# source_eagle.net
KiCad netlist of a schematic drawn in EAGLE
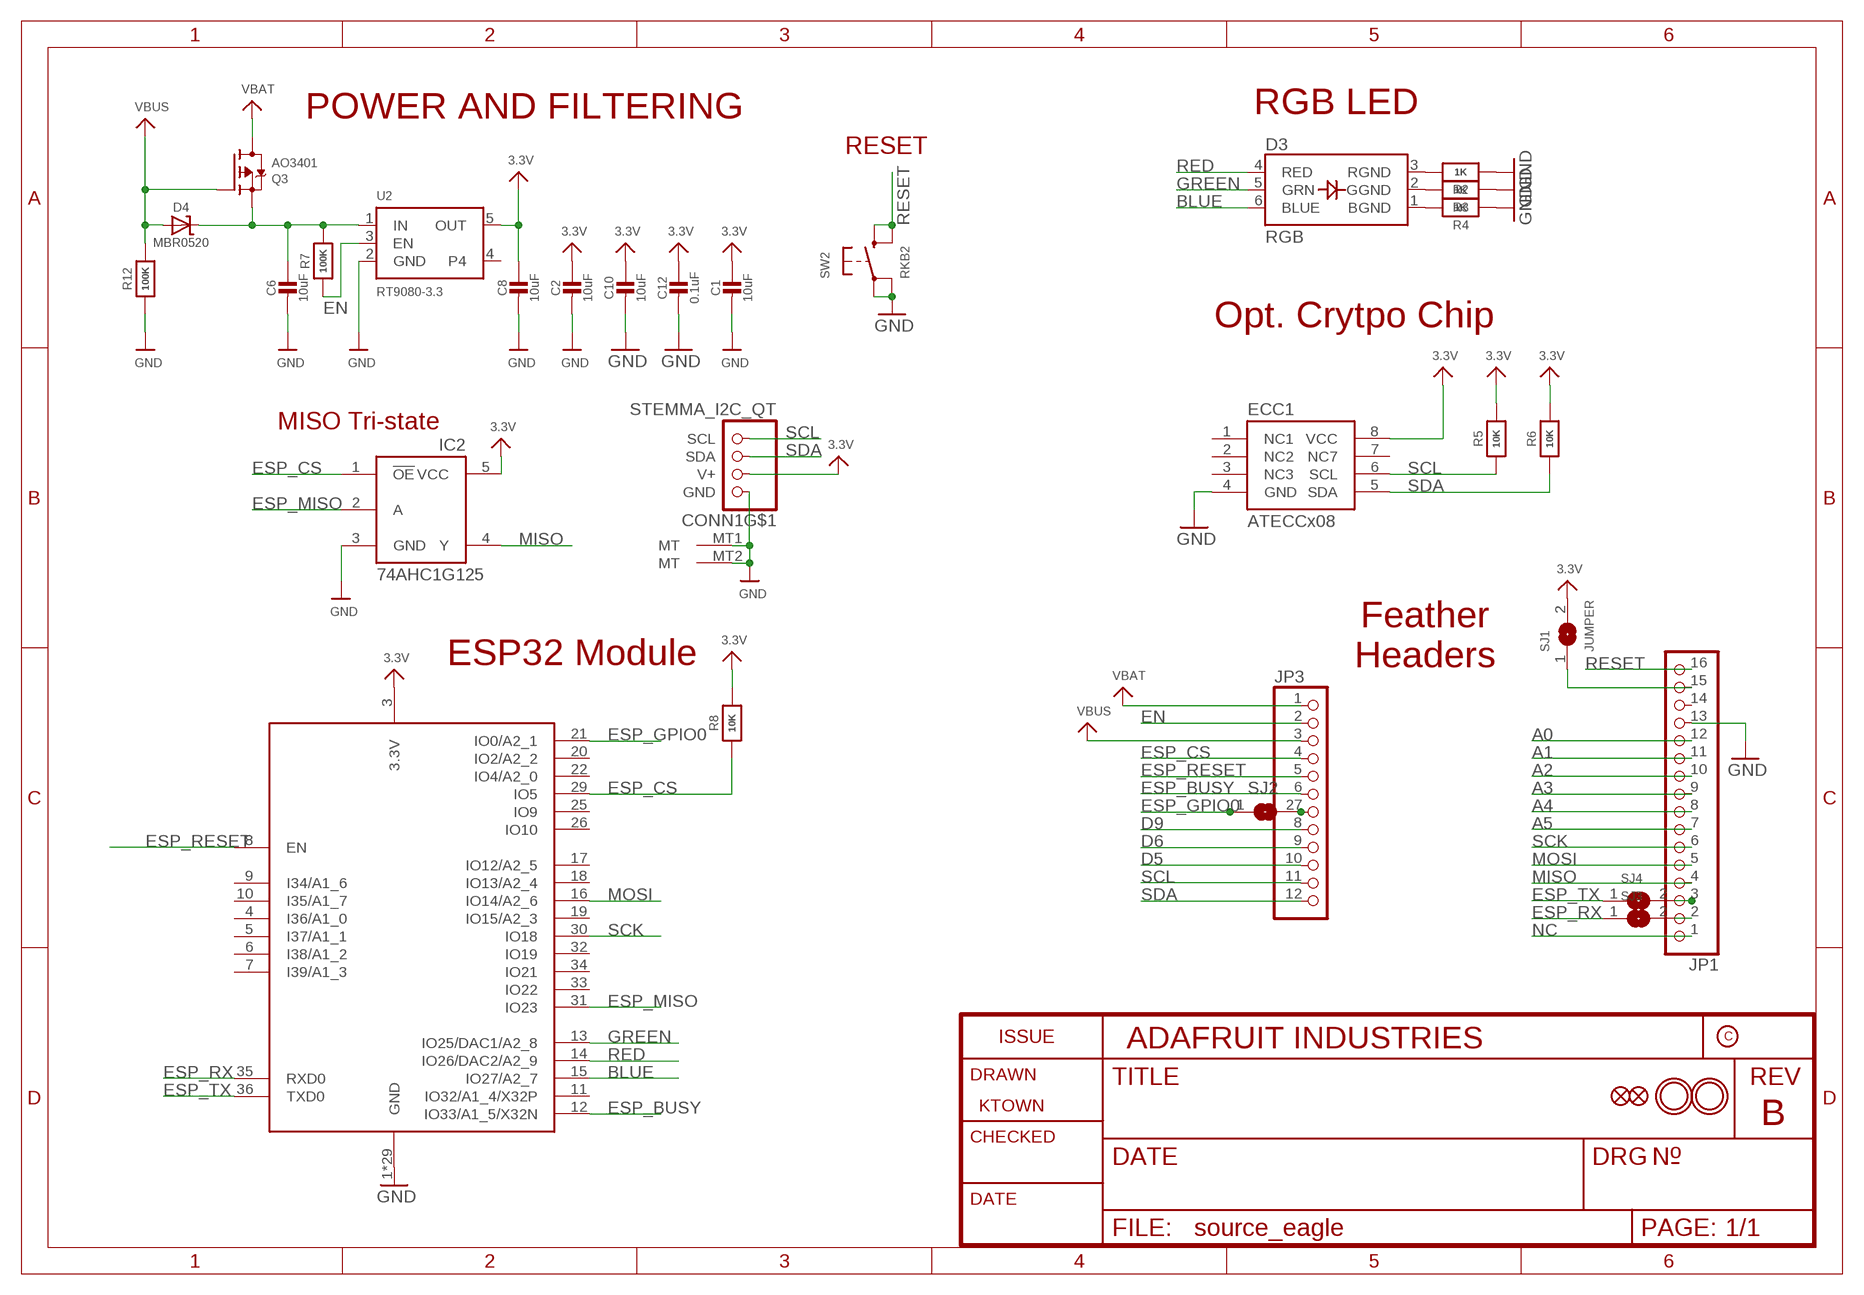
[diagram p0: schematic, sheet 1]

(export (version "E")
  (design (tool "Eeschema 10.0.6"))
  (components
    (comp (ref "C1")
      (value "10uF")
      (footprint "eagle-import:0805-NO")
      (libsource (lib "eagle-import") (part "CAP_CERAMIC0805-NOOUTLINE"))
    )
    (comp (ref "C2")
      (value "10uF")
      (footprint "eagle-import:0805-NO")
      (libsource (lib "eagle-import") (part "CAP_CERAMIC0805-NOOUTLINE"))
    )
    (comp (ref "C6")
      (value "10uF")
      (footprint "eagle-import:0805-NO")
      (libsource (lib "eagle-import") (part "CAP_CERAMIC0805-NOOUTLINE"))
    )
    (comp (ref "C8")
      (value "10uF")
      (footprint "eagle-import:0805-NO")
      (fields (field (name "REV") "C"))
      (libsource (lib "eagle-import") (part "CAP_CERAMIC0805-NOOUTLINE"))
    )
    (comp (ref "C10")
      (value "10uF")
      (footprint "eagle-import:0805-NO")
      (libsource (lib "eagle-import") (part "CAP_CERAMIC0805-NOOUTLINE"))
    )
    (comp (ref "C12")
      (value "0.1uF")
      (footprint "eagle-import:0603-NO")
      (libsource (lib "eagle-import") (part "CAP_CERAMIC0603_NO"))
    )
    (comp (ref "CONN1")
      (value "STEMMA_I2C_QT")
      (footprint "eagle-import:JST_SH4")
      (libsource (lib "eagle-import") (part "STEMMA_I2C_QT"))
    )
    (comp (ref "D3")
      (value "RGB")
      (footprint "eagle-import:RGBLED_3535_PLCC6")
      (libsource (lib "eagle-import") (part "LED_RGB_PLCC63535"))
    )
    (comp (ref "D4")
      (value "MBR0520")
      (footprint "eagle-import:SOD-123")
      (libsource (lib "eagle-import") (part "DIODE-SCHOTTKYSOD-123"))
    )
    (comp (ref "ECC1")
      (value "ATECCx08")
      (footprint "eagle-import:SOIC8")
      (libsource (lib "eagle-import") (part "ATECC108"))
    )
    (comp (ref "IC2")
      (value "74AHC1G125")
      (footprint "eagle-import:SOT23-5L")
      (libsource (lib "eagle-import") (part "74AHC1G125"))
    )
    (comp (ref "JP1")
      (value "HEADER-1X16_MIN")
      (footprint "eagle-import:1X16_ROUND_MIN")
      (libsource (lib "eagle-import") (part "HEADER-1X16_MIN"))
    )
    (comp (ref "JP3")
      (value "HEADER-1X12_MIN")
      (footprint "eagle-import:1X12_ROUND_MIN")
      (libsource (lib "eagle-import") (part "HEADER-1X12_MIN"))
    )
    (comp (ref "Q3")
      (value "AO3401")
      (footprint "eagle-import:SOT23-R")
      (libsource (lib "eagle-import") (part "MOSFET-P"))
    )
    (comp (ref "R2")
      (value "1K")
      (footprint "eagle-import:0603-NO")
      (libsource (lib "eagle-import") (part "RESISTOR_0603_NOOUT"))
    )
    (comp (ref "R3")
      (value "1K")
      (footprint "eagle-import:0603-NO")
      (libsource (lib "eagle-import") (part "RESISTOR_0603_NOOUT"))
    )
    (comp (ref "R4")
      (value "1K")
      (footprint "eagle-import:0603-NO")
      (libsource (lib "eagle-import") (part "RESISTOR_0603_NOOUT"))
    )
    (comp (ref "R5")
      (value "10K")
      (footprint "eagle-import:0603-NO")
      (libsource (lib "eagle-import") (part "RESISTOR_0603_NOOUT"))
    )
    (comp (ref "R6")
      (value "10K")
      (footprint "eagle-import:0603-NO")
      (libsource (lib "eagle-import") (part "RESISTOR_0603_NOOUT"))
    )
    (comp (ref "R7")
      (value "100K")
      (footprint "eagle-import:0603-NO")
      (libsource (lib "eagle-import") (part "RESISTOR_0603_NOOUT"))
    )
    (comp (ref "R8")
      (value "10K")
      (footprint "eagle-import:0603-NO")
      (libsource (lib "eagle-import") (part "RESISTOR_0603_NOOUT"))
    )
    (comp (ref "R12")
      (value "100K")
      (footprint "eagle-import:0603-NO")
      (libsource (lib "eagle-import") (part "RESISTOR_0603_NOOUT"))
    )
    (comp (ref "SJ1")
      (value "JUMPER")
      (footprint "eagle-import:SOLDERJUMPER_ARROW_NOPASTE")
      (libsource (lib "eagle-import") (part "SOLDERJUMPER"))
    )
    (comp (ref "SJ2")
      (value "SOLDERJUMPER")
      (footprint "eagle-import:SOLDERJUMPER_ARROW_NOPASTE")
      (libsource (lib "eagle-import") (part "SOLDERJUMPER"))
    )
    (comp (ref "SJ3")
      (value "SOLDERJUMPER")
      (footprint "eagle-import:SOLDERJUMPER_ARROW_NOPASTE")
      (libsource (lib "eagle-import") (part "SOLDERJUMPER"))
    )
    (comp (ref "SJ4")
      (value "SOLDERJUMPER")
      (footprint "eagle-import:SOLDERJUMPER_ARROW_NOPASTE")
      (libsource (lib "eagle-import") (part "SOLDERJUMPER"))
    )
    (comp (ref "SW2")
      (value "RKB2")
      (footprint "eagle-import:BTN_RKB2_4.6X2.8")
      (libsource (lib "eagle-import") (part "SWITCH_TACT_SMT_RKB2"))
    )
    (comp (ref "U$31")
      (value "MOUNTINGHOLE2.5")
      (footprint "eagle-import:MOUNTINGHOLE_2.5_PLATED")
      (libsource (lib "eagle-import") (part "MOUNTINGHOLE2.5"))
    )
    (comp (ref "U$32")
      (value "MOUNTINGHOLE2.5")
      (footprint "eagle-import:MOUNTINGHOLE_2.5_PLATED")
      (libsource (lib "eagle-import") (part "MOUNTINGHOLE2.5"))
    )
    (comp (ref "U$34")
      (value "FIDUCIAL_1MM")
      (footprint "eagle-import:FIDUCIAL_1MM")
      (libsource (lib "eagle-import") (part "FIDUCIAL_1MM"))
    )
    (comp (ref "U$35")
      (value "FIDUCIAL_1MM")
      (footprint "eagle-import:FIDUCIAL_1MM")
      (libsource (lib "eagle-import") (part "FIDUCIAL_1MM"))
    )
    (comp (ref "U2")
      (value "RT9080-3.3")
      (footprint "eagle-import:SOT23-5")
      (fields (field (name "JLC_ROTATION") "0"))
      (libsource (lib "eagle-import") (part "VREG_SOT23-5"))
    )
    (comp (ref "X1")
      (value "ESP32-MINI-1")
      (footprint "eagle-import:ESP32-MINI-1")
      (libsource (lib "eagle-import") (part "ESP32-MINI-1"))
    )
  )
  (nets
    (net (code "1") (name "/A0") (class "Default")
      (node (ref "JP1") (pin "12") (pinfunction "12_12") (pintype "passive"))
    )
    (net (code "2") (name "/A1") (class "Default")
      (node (ref "JP1") (pin "11") (pinfunction "11_11") (pintype "passive"))
    )
    (net (code "3") (name "/A2") (class "Default")
      (node (ref "JP1") (pin "10") (pinfunction "10_10") (pintype "passive"))
    )
    (net (code "4") (name "/A3") (class "Default")
      (node (ref "JP1") (pin "9") (pinfunction "9_9") (pintype "passive"))
    )
    (net (code "5") (name "/A4") (class "Default")
      (node (ref "JP1") (pin "8") (pinfunction "8_8") (pintype "passive"))
    )
    (net (code "6") (name "/A5") (class "Default")
      (node (ref "JP1") (pin "7") (pinfunction "7_7") (pintype "passive"))
    )
    (net (code "7") (name "/BLUE") (class "Default")
      (node (ref "D3") (pin "6") (pinfunction "BLUE_6") (pintype "bidirectional"))
      (node (ref "X1") (pin "15") (pinfunction "IO27/A2_7_15") (pintype "bidirectional"))
    )
    (net (code "8") (name "/D5") (class "Default")
      (node (ref "JP3") (pin "10") (pinfunction "10_10") (pintype "passive"))
    )
    (net (code "9") (name "/D6") (class "Default")
      (node (ref "JP3") (pin "9") (pinfunction "9_9") (pintype "passive"))
    )
    (net (code "10") (name "/D9") (class "Default")
      (node (ref "JP3") (pin "8") (pinfunction "8_8") (pintype "passive"))
    )
    (net (code "11") (name "/EN") (class "Default")
      (node (ref "JP3") (pin "2") (pinfunction "2_2") (pintype "passive"))
      (node (ref "R7") (pin "1") (pinfunction "1_1") (pintype "passive"))
      (node (ref "U2") (pin "3") (pinfunction "EN_3") (pintype "input"))
    )
    (net (code "12") (name "/ESP_BUSY") (class "Default")
      (node (ref "JP3") (pin "6") (pinfunction "6_6") (pintype "passive"))
      (node (ref "X1") (pin "12") (pinfunction "IO33/A1_5/X32N_12") (pintype "bidirectional"))
    )
    (net (code "13") (name "/ESP_CS") (class "Default")
      (node (ref "IC2") (pin "1") (pinfunction "~{OE}_1") (pintype "input"))
      (node (ref "JP3") (pin "4") (pinfunction "4_4") (pintype "passive"))
      (node (ref "R8") (pin "1") (pinfunction "1_1") (pintype "passive"))
      (node (ref "X1") (pin "29") (pinfunction "IO5_29") (pintype "bidirectional"))
    )
    (net (code "14") (name "/ESP_GPIO0") (class "Default")
      (node (ref "SJ2") (pin "1") (pinfunction "1_1") (pintype "passive"))
      (node (ref "X1") (pin "21") (pinfunction "IO0/A2_1_21") (pintype "bidirectional"))
    )
    (net (code "15") (name "/ESP_MISO") (class "Default")
      (node (ref "IC2") (pin "2") (pinfunction "A_2") (pintype "input"))
      (node (ref "X1") (pin "31") (pinfunction "IO23_31") (pintype "bidirectional"))
    )
    (net (code "16") (name "/ESP_RESET") (class "Default")
      (node (ref "JP3") (pin "5") (pinfunction "5_5") (pintype "passive"))
      (node (ref "X1") (pin "8") (pinfunction "EN_8") (pintype "input"))
    )
    (net (code "17") (name "/ESP_RX") (class "Default")
      (node (ref "SJ3") (pin "1") (pinfunction "1_1") (pintype "passive"))
      (node (ref "X1") (pin "35") (pinfunction "RXD0_35") (pintype "input"))
    )
    (net (code "18") (name "/ESP_TX") (class "Default")
      (node (ref "SJ4") (pin "1") (pinfunction "1_1") (pintype "passive"))
      (node (ref "X1") (pin "36") (pinfunction "TXD0_36") (pintype "output"))
    )
    (net (code "19") (name "/GREEN") (class "Default")
      (node (ref "D3") (pin "5") (pinfunction "GRN_5") (pintype "bidirectional"))
      (node (ref "X1") (pin "13") (pinfunction "IO25/DAC1/A2_8_13") (pintype "bidirectional"))
    )
    (net (code "20") (name "/MISO") (class "Default")
      (node (ref "IC2") (pin "4") (pinfunction "Y_4") (pintype "output"))
      (node (ref "JP1") (pin "4") (pinfunction "4_4") (pintype "passive"))
    )
    (net (code "21") (name "/MOSI") (class "Default")
      (node (ref "JP1") (pin "5") (pinfunction "5_5") (pintype "passive"))
      (node (ref "X1") (pin "16") (pinfunction "IO14/A2_6_16") (pintype "bidirectional"))
    )
    (net (code "22") (name "/NC") (class "Default")
      (node (ref "JP1") (pin "1") (pinfunction "1_1") (pintype "passive"))
    )
    (net (code "23") (name "/RED") (class "Default")
      (node (ref "D3") (pin "4") (pinfunction "RED_4") (pintype "bidirectional"))
      (node (ref "X1") (pin "14") (pinfunction "IO26/DAC2/A2_9_14") (pintype "bidirectional"))
    )
    (net (code "24") (name "/RESET") (class "Default")
      (node (ref "JP1") (pin "16") (pinfunction "16_16") (pintype "passive"))
      (node (ref "SW2") (pin "B") (pinfunction "S_B") (pintype "passive"))
      (node (ref "SW2") (pin "B'") (pinfunction "S1_B'") (pintype "passive"))
    )
    (net (code "25") (name "/SCK") (class "Default")
      (node (ref "JP1") (pin "6") (pinfunction "6_6") (pintype "passive"))
      (node (ref "X1") (pin "30") (pinfunction "IO18_30") (pintype "bidirectional"))
    )
    (net (code "26") (name "/SCL") (class "Default")
      (node (ref "CONN1") (pin "4") (pinfunction "SCL_4") (pintype "passive"))
      (node (ref "ECC1") (pin "6") (pinfunction "SCL_6") (pintype "bidirectional"))
      (node (ref "JP3") (pin "11") (pinfunction "11_11") (pintype "passive"))
      (node (ref "R5") (pin "1") (pinfunction "1_1") (pintype "passive"))
    )
    (net (code "27") (name "/SDA") (class "Default")
      (node (ref "CONN1") (pin "3") (pinfunction "SDA_3") (pintype "passive"))
      (node (ref "ECC1") (pin "5") (pinfunction "SDA_5") (pintype "bidirectional"))
      (node (ref "JP3") (pin "12") (pinfunction "12_12") (pintype "passive"))
      (node (ref "R6") (pin "1") (pinfunction "1_1") (pintype "passive"))
    )
    (net (code "28") (name "3.3V") (class "Default")
      (node (ref "C1") (pin "1") (pinfunction "1_1") (pintype "passive"))
      (node (ref "C10") (pin "1") (pinfunction "1_1") (pintype "passive"))
      (node (ref "C12") (pin "1") (pinfunction "1_1") (pintype "passive"))
      (node (ref "C2") (pin "1") (pinfunction "1_1") (pintype "passive"))
      (node (ref "C8") (pin "1") (pinfunction "1_1") (pintype "passive"))
      (node (ref "CONN1") (pin "2") (pinfunction "V+_2") (pintype "passive"))
      (node (ref "ECC1") (pin "8") (pinfunction "VCC_8") (pintype "power_in"))
      (node (ref "IC2") (pin "5") (pinfunction "VCC_5") (pintype "power_in"))
      (node (ref "R5") (pin "2") (pinfunction "2_2") (pintype "passive"))
      (node (ref "R6") (pin "2") (pinfunction "2_2") (pintype "passive"))
      (node (ref "R8") (pin "2") (pinfunction "2_2") (pintype "passive"))
      (node (ref "SJ1") (pin "2") (pinfunction "2_2") (pintype "passive"))
      (node (ref "U2") (pin "5") (pinfunction "OUT_5") (pintype "power_in"))
      (node (ref "X1") (pin "3") (pinfunction "3.3V_3") (pintype "passive"))
    )
    (net (code "29") (name "GND") (class "Default")
      (node (ref "C1") (pin "2") (pinfunction "2_2") (pintype "passive"))
      (node (ref "C10") (pin "2") (pinfunction "2_2") (pintype "passive"))
      (node (ref "C12") (pin "2") (pinfunction "2_2") (pintype "passive"))
      (node (ref "C2") (pin "2") (pinfunction "2_2") (pintype "passive"))
      (node (ref "C6") (pin "2") (pinfunction "2_2") (pintype "passive"))
      (node (ref "C8") (pin "2") (pinfunction "2_2") (pintype "passive"))
      (node (ref "CONN1") (pin "1") (pinfunction "GND_1") (pintype "passive"))
      (node (ref "CONN1") (pin "MT1") (pinfunction "MT_MT1") (pintype "bidirectional"))
      (node (ref "CONN1") (pin "MT2") (pinfunction "MT_MT2") (pintype "bidirectional"))
      (node (ref "ECC1") (pin "4") (pinfunction "GND_4") (pintype "power_in"))
      (node (ref "IC2") (pin "3") (pinfunction "GND_3") (pintype "power_in"))
      (node (ref "JP1") (pin "13") (pinfunction "13_13") (pintype "passive"))
      (node (ref "R12") (pin "1") (pinfunction "1_1") (pintype "passive"))
      (node (ref "R2") (pin "1") (pinfunction "1_1") (pintype "passive"))
      (node (ref "R3") (pin "1") (pinfunction "1_1") (pintype "passive"))
      (node (ref "R4") (pin "1") (pinfunction "1_1") (pintype "passive"))
      (node (ref "SW2") (pin "A") (pinfunction "P_A") (pintype "passive"))
      (node (ref "SW2") (pin "A'") (pinfunction "P1_A'") (pintype "passive"))
      (node (ref "U2") (pin "2") (pinfunction "GND_2") (pintype "power_in"))
      (node (ref "X1") (pin "1") (pinfunction "GND_1") (pintype "passive"))
      (node (ref "X1") (pin "2") (pinfunction "GND_2") (pintype "passive"))
      (node (ref "X1") (pin "27") (pinfunction "GND_27") (pintype "passive"))
      (node (ref "X1") (pin "38") (pinfunction "GND_38") (pintype "passive"))
      (node (ref "X1") (pin "39") (pinfunction "GND_39") (pintype "passive"))
      (node (ref "X1") (pin "40") (pinfunction "GND_40") (pintype "passive"))
      (node (ref "X1") (pin "41") (pinfunction "GND_41") (pintype "passive"))
      (node (ref "X1") (pin "42") (pinfunction "GND_42") (pintype "passive"))
      (node (ref "X1") (pin "43") (pinfunction "GND_43") (pintype "passive"))
      (node (ref "X1") (pin "44") (pinfunction "GND_44") (pintype "passive"))
      (node (ref "X1") (pin "45") (pinfunction "GND_45") (pintype "passive"))
      (node (ref "X1") (pin "46") (pinfunction "GND_46") (pintype "passive"))
      (node (ref "X1") (pin "47") (pinfunction "GND_47") (pintype "passive"))
      (node (ref "X1") (pin "48") (pinfunction "GND_48") (pintype "passive"))
      (node (ref "X1") (pin "49") (pinfunction "GND_49") (pintype "passive"))
      (node (ref "X1") (pin "50") (pinfunction "GND_50") (pintype "passive"))
      (node (ref "X1") (pin "51") (pinfunction "GND_51") (pintype "passive"))
      (node (ref "X1") (pin "52") (pinfunction "GND_52") (pintype "passive"))
      (node (ref "X1") (pin "53") (pinfunction "GND_53") (pintype "passive"))
      (node (ref "X1") (pin "54") (pinfunction "GND_54") (pintype "passive"))
      (node (ref "X1") (pin "55") (pinfunction "GND_55") (pintype "passive"))
      (node (ref "X1") (pin "56") (pinfunction "GND_56") (pintype "passive"))
      (node (ref "X1") (pin "57") (pinfunction "GND_57") (pintype "passive"))
      (node (ref "X1") (pin "58") (pinfunction "GND_58") (pintype "passive"))
      (node (ref "X1") (pin "59") (pinfunction "GND_59") (pintype "passive"))
      (node (ref "X1") (pin "60") (pinfunction "GND_60") (pintype "passive"))
      (node (ref "X1") (pin "61") (pinfunction "GND_61") (pintype "passive"))
      (node (ref "X1") (pin "62") (pinfunction "GND_62") (pintype "passive"))
      (node (ref "X1") (pin "63") (pinfunction "GND_63") (pintype "passive"))
    )
    (net (code "30") (name "Net-(D3-BGND)") (class "Default")
      (node (ref "D3") (pin "1") (pinfunction "BGND_1") (pintype "power_in"))
      (node (ref "R4") (pin "2") (pinfunction "2_2") (pintype "passive"))
    )
    (net (code "31") (name "Net-(D3-GGND)") (class "Default")
      (node (ref "D3") (pin "2") (pinfunction "GGND_2") (pintype "power_in"))
      (node (ref "R3") (pin "2") (pinfunction "2_2") (pintype "passive"))
    )
    (net (code "32") (name "Net-(D3-RGND)") (class "Default")
      (node (ref "D3") (pin "3") (pinfunction "RGND_3") (pintype "power_in"))
      (node (ref "R2") (pin "2") (pinfunction "2_2") (pintype "passive"))
    )
    (net (code "33") (name "Net-(JP1-Pad2)") (class "Default")
      (node (ref "JP1") (pin "2") (pinfunction "2_2") (pintype "passive"))
      (node (ref "SJ3") (pin "2") (pinfunction "2_2") (pintype "passive"))
    )
    (net (code "34") (name "Net-(JP1-Pad3)") (class "Default")
      (node (ref "JP1") (pin "3") (pinfunction "3_3") (pintype "passive"))
      (node (ref "SJ4") (pin "2") (pinfunction "2_2") (pintype "passive"))
    )
    (net (code "35") (name "Net-(JP1-Pad15)") (class "Default")
      (node (ref "JP1") (pin "15") (pinfunction "15_15") (pintype "passive"))
      (node (ref "SJ1") (pin "1") (pinfunction "1_1") (pintype "passive"))
    )
    (net (code "36") (name "Net-(JP3-Pad7)") (class "Default")
      (node (ref "JP3") (pin "7") (pinfunction "7_7") (pintype "passive"))
      (node (ref "SJ2") (pin "2") (pinfunction "2_2") (pintype "passive"))
    )
    (net (code "37") (name "Net-(Q3-S)") (class "Default")
      (node (ref "C6") (pin "1") (pinfunction "1_1") (pintype "passive"))
      (node (ref "D4") (pin "C") (pinfunction "C_C") (pintype "passive"))
      (node (ref "Q3") (pin "2") (pinfunction "S_2") (pintype "passive"))
      (node (ref "R7") (pin "2") (pinfunction "2_2") (pintype "passive"))
      (node (ref "U2") (pin "1") (pinfunction "IN_1") (pintype "power_in"))
    )
    (net (code "38") (name "VBAT") (class "Default")
      (node (ref "JP3") (pin "1") (pinfunction "1_1") (pintype "passive"))
      (node (ref "Q3") (pin "3") (pinfunction "D_3") (pintype "passive"))
    )
    (net (code "39") (name "VBUS") (class "Default")
      (node (ref "D4") (pin "A") (pinfunction "A_A") (pintype "passive"))
      (node (ref "JP3") (pin "3") (pinfunction "3_3") (pintype "passive"))
      (node (ref "Q3") (pin "1") (pinfunction "G_1") (pintype "passive"))
      (node (ref "R12") (pin "2") (pinfunction "2_2") (pintype "passive"))
    )
    (net (code "40") (name "unconnected-(ECC1-NC1-Pad1)") (class "Default")
      (node (ref "ECC1") (pin "1") (pinfunction "NC1_1") (pintype "bidirectional"))
    )
    (net (code "41") (name "unconnected-(ECC1-NC2-Pad2)") (class "Default")
      (node (ref "ECC1") (pin "2") (pinfunction "NC2_2") (pintype "no_connect"))
    )
    (net (code "42") (name "unconnected-(ECC1-NC3-Pad3)") (class "Default")
      (node (ref "ECC1") (pin "3") (pinfunction "NC3_3") (pintype "no_connect"))
    )
    (net (code "43") (name "unconnected-(ECC1-NC7-Pad7)") (class "Default")
      (node (ref "ECC1") (pin "7") (pinfunction "NC7_7") (pintype "no_connect"))
    )
    (net (code "44") (name "unconnected-(JP1-Pad14)") (class "Default")
      (node (ref "JP1") (pin "14") (pinfunction "14_14") (pintype "passive"))
    )
    (net (code "45") (name "unconnected-(U2-P4-Pad4)") (class "Default")
      (node (ref "U2") (pin "4") (pinfunction "P4_4") (pintype "bidirectional"))
    )
    (net (code "46") (name "unconnected-(X1-I34{slash}A1_6-Pad9)") (class "Default")
      (node (ref "X1") (pin "9") (pinfunction "I34/A1_6_9") (pintype "input"))
    )
    (net (code "47") (name "unconnected-(X1-I35{slash}A1_7-Pad10)") (class "Default")
      (node (ref "X1") (pin "10") (pinfunction "I35/A1_7_10") (pintype "input"))
    )
    (net (code "48") (name "unconnected-(X1-I36{slash}A1_0-Pad4)") (class "Default")
      (node (ref "X1") (pin "4") (pinfunction "I36/A1_0_4") (pintype "input"))
    )
    (net (code "49") (name "unconnected-(X1-I37{slash}A1_1-Pad5)") (class "Default")
      (node (ref "X1") (pin "5") (pinfunction "I37/A1_1_5") (pintype "input"))
    )
    (net (code "50") (name "unconnected-(X1-I38{slash}A1_2-Pad6)") (class "Default")
      (node (ref "X1") (pin "6") (pinfunction "I38/A1_2_6") (pintype "input"))
    )
    (net (code "51") (name "unconnected-(X1-I39{slash}A1_3-Pad7)") (class "Default")
      (node (ref "X1") (pin "7") (pinfunction "I39/A1_3_7") (pintype "input"))
    )
    (net (code "52") (name "unconnected-(X1-IO2{slash}A2_2-Pad20)") (class "Default")
      (node (ref "X1") (pin "20") (pinfunction "IO2/A2_2_20") (pintype "bidirectional"))
    )
    (net (code "53") (name "unconnected-(X1-IO4{slash}A2_0-Pad22)") (class "Default")
      (node (ref "X1") (pin "22") (pinfunction "IO4/A2_0_22") (pintype "bidirectional"))
    )
    (net (code "54") (name "unconnected-(X1-IO9-Pad25)") (class "Default")
      (node (ref "X1") (pin "25") (pinfunction "IO9_25") (pintype "bidirectional"))
    )
    (net (code "55") (name "unconnected-(X1-IO10-Pad26)") (class "Default")
      (node (ref "X1") (pin "26") (pinfunction "IO10_26") (pintype "bidirectional"))
    )
    (net (code "56") (name "unconnected-(X1-IO12{slash}A2_5-Pad17)") (class "Default")
      (node (ref "X1") (pin "17") (pinfunction "IO12/A2_5_17") (pintype "bidirectional"))
    )
    (net (code "57") (name "unconnected-(X1-IO13{slash}A2_4-Pad18)") (class "Default")
      (node (ref "X1") (pin "18") (pinfunction "IO13/A2_4_18") (pintype "bidirectional"))
    )
    (net (code "58") (name "unconnected-(X1-IO15{slash}A2_3-Pad19)") (class "Default")
      (node (ref "X1") (pin "19") (pinfunction "IO15/A2_3_19") (pintype "bidirectional"))
    )
    (net (code "59") (name "unconnected-(X1-IO19-Pad32)") (class "Default")
      (node (ref "X1") (pin "32") (pinfunction "IO19_32") (pintype "bidirectional"))
    )
    (net (code "60") (name "unconnected-(X1-IO21-Pad34)") (class "Default")
      (node (ref "X1") (pin "34") (pinfunction "IO21_34") (pintype "bidirectional"))
    )
    (net (code "61") (name "unconnected-(X1-IO22-Pad33)") (class "Default")
      (node (ref "X1") (pin "33") (pinfunction "IO22_33") (pintype "bidirectional"))
    )
    (net (code "62") (name "unconnected-(X1-IO32{slash}A1_4{slash}X32P-Pad11)") (class "Default")
      (node (ref "X1") (pin "11") (pinfunction "IO32/A1_4/X32P_11") (pintype "bidirectional"))
    )
  )
)
